# Mako_DSP_QuadFlash_and_Boot_R2_1.net
KiCad netlist of a schematic drawn in Altium Designer
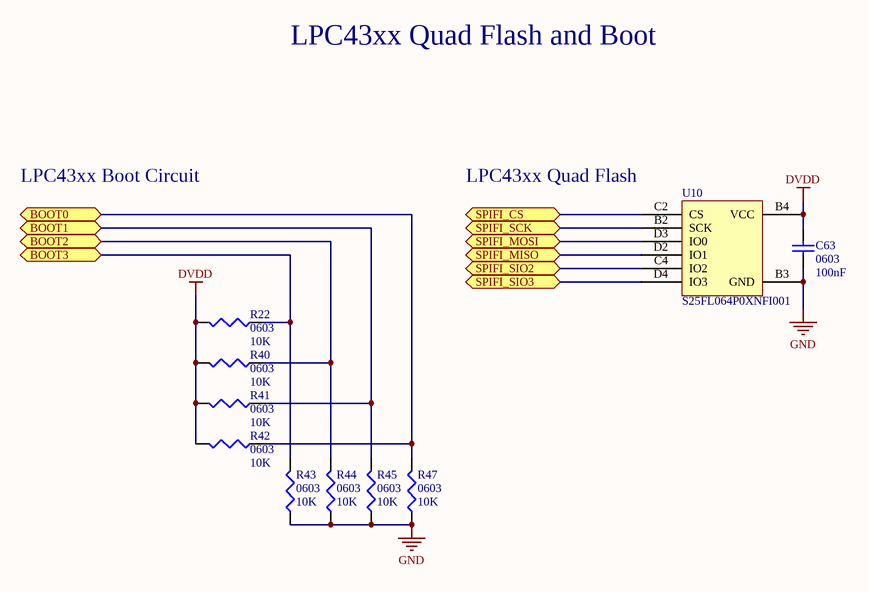
[diagram p0: Mako DSP QuadFlash and Boot R2.1.SchDoc]

(export (version "E")
  (design (tool "Eeschema 10.0.6"))
  (components
    (comp (ref "C63")
      (value "0603")
      (footprint "1608[0603]")
      (description "Capacitor (Semiconductor SIM Model)")
      (fields (field (name "ALTIUM_VALUE") "100nF") (field (name "PUBLISHER") "Altium Limited"))
      (libsource (lib "Miscellaneous Devices") (part "Cap Semi"))
    )
    (comp (ref "R22")
      (value "0603")
      (footprint "J1-0603")
      (description "Resistor")
      (fields (field (name "ALTIUM_VALUE") "10K") (field (name "PUBLISHER") "Altium Limited"))
      (libsource (lib "Miscellaneous Devices") (part "Res3"))
    )
    (comp (ref "R40")
      (value "0603")
      (footprint "J1-0603")
      (description "Resistor")
      (fields (field (name "ALTIUM_VALUE") "10K") (field (name "PUBLISHER") "Altium Limited"))
      (libsource (lib "Miscellaneous Devices") (part "Res3"))
    )
    (comp (ref "R41")
      (value "0603")
      (footprint "J1-0603")
      (description "Resistor")
      (fields (field (name "ALTIUM_VALUE") "10K") (field (name "PUBLISHER") "Altium Limited"))
      (libsource (lib "Miscellaneous Devices") (part "Res3"))
    )
    (comp (ref "R42")
      (value "0603")
      (footprint "J1-0603")
      (description "Resistor")
      (fields (field (name "ALTIUM_VALUE") "10K") (field (name "PUBLISHER") "Altium Limited"))
      (libsource (lib "Miscellaneous Devices") (part "Res3"))
    )
    (comp (ref "R43")
      (value "0603")
      (footprint "J1-0603")
      (description "Resistor")
      (fields (field (name "ALTIUM_VALUE") "10K") (field (name "PUBLISHER") "Altium Limited"))
      (libsource (lib "Miscellaneous Devices") (part "Res3"))
    )
    (comp (ref "R44")
      (value "0603")
      (footprint "J1-0603")
      (description "Resistor")
      (fields (field (name "ALTIUM_VALUE") "10K") (field (name "PUBLISHER") "Altium Limited"))
      (libsource (lib "Miscellaneous Devices") (part "Res3"))
    )
    (comp (ref "R45")
      (value "0603")
      (footprint "J1-0603")
      (description "Resistor")
      (fields (field (name "ALTIUM_VALUE") "10K") (field (name "PUBLISHER") "Altium Limited"))
      (libsource (lib "Miscellaneous Devices") (part "Res3"))
    )
    (comp (ref "R47")
      (value "0603")
      (footprint "J1-0603")
      (description "Resistor")
      (fields (field (name "ALTIUM_VALUE") "10K") (field (name "PUBLISHER") "Altium Limited"))
      (libsource (lib "Miscellaneous Devices") (part "Res3"))
    )
    (comp (ref "U10")
      (value "S25FL064P0XNFI001")
      (footprint "S25FL064P0XNFI001")
      (description "SPIFI Quad Flash")
      (libsource (lib "Mako DSP Schematic Library") (part "S25FL064P0XNFI001"))
    )
  )
  (nets
    (net (code "1") (name "/BOOT0") (class "Default")
      (node (ref "R42") (pin "1") (pinfunction "1_1") (pintype "passive"))
      (node (ref "R47") (pin "2") (pinfunction "2_2") (pintype "passive"))
    )
    (net (code "2") (name "/BOOT1") (class "Default")
      (node (ref "R41") (pin "1") (pinfunction "1_1") (pintype "passive"))
      (node (ref "R45") (pin "2") (pinfunction "2_2") (pintype "passive"))
    )
    (net (code "3") (name "/BOOT2") (class "Default")
      (node (ref "R40") (pin "1") (pinfunction "1_1") (pintype "passive"))
      (node (ref "R44") (pin "2") (pinfunction "2_2") (pintype "passive"))
    )
    (net (code "4") (name "/BOOT3") (class "Default")
      (node (ref "R22") (pin "1") (pinfunction "1_1") (pintype "passive"))
      (node (ref "R43") (pin "2") (pinfunction "2_2") (pintype "passive"))
    )
    (net (code "5") (name "/SPIFI_CS") (class "Default")
      (node (ref "U10") (pin "C2") (pinfunction "CS_C2") (pintype "passive"))
    )
    (net (code "6") (name "/SPIFI_MISO") (class "Default")
      (node (ref "U10") (pin "D2") (pinfunction "IO1_D2") (pintype "passive"))
    )
    (net (code "7") (name "/SPIFI_MOSI") (class "Default")
      (node (ref "U10") (pin "D3") (pinfunction "IO0_D3") (pintype "passive"))
    )
    (net (code "8") (name "/SPIFI_SCK") (class "Default")
      (node (ref "U10") (pin "B2") (pinfunction "SCK_B2") (pintype "passive"))
    )
    (net (code "9") (name "/SPIFI_SIO2") (class "Default")
      (node (ref "U10") (pin "C4") (pinfunction "IO2_C4") (pintype "passive"))
    )
    (net (code "10") (name "/SPIFI_SIO3") (class "Default")
      (node (ref "U10") (pin "D4") (pinfunction "IO3_D4") (pintype "passive"))
    )
    (net (code "11") (name "DVDD") (class "Default")
      (node (ref "C63") (pin "2") (pinfunction "2_2") (pintype "passive"))
      (node (ref "R22") (pin "2") (pinfunction "2_2") (pintype "passive"))
      (node (ref "R40") (pin "2") (pinfunction "2_2") (pintype "passive"))
      (node (ref "R41") (pin "2") (pinfunction "2_2") (pintype "passive"))
      (node (ref "R42") (pin "2") (pinfunction "2_2") (pintype "passive"))
      (node (ref "U10") (pin "B4") (pinfunction "VCC_B4") (pintype "passive"))
    )
    (net (code "12") (name "GND") (class "Default")
      (node (ref "C63") (pin "1") (pinfunction "1_1") (pintype "passive"))
      (node (ref "R43") (pin "1") (pinfunction "1_1") (pintype "passive"))
      (node (ref "R44") (pin "1") (pinfunction "1_1") (pintype "passive"))
      (node (ref "R45") (pin "1") (pinfunction "1_1") (pintype "passive"))
      (node (ref "R47") (pin "1") (pinfunction "1_1") (pintype "passive"))
      (node (ref "U10") (pin "B3") (pinfunction "GND_B3") (pintype "passive"))
    )
    (net (code "13") (name "unconnected-(U10-NC-PadA2)") (class "Default")
      (node (ref "U10") (pin "A2") (pinfunction "NC_A2") (pintype "passive"))
    )
    (net (code "14") (name "unconnected-(U10-NC-PadA3)") (class "Default")
      (node (ref "U10") (pin "A3") (pinfunction "NC_A3") (pintype "passive"))
    )
    (net (code "15") (name "unconnected-(U10-NC-PadA4)") (class "Default")
      (node (ref "U10") (pin "A4") (pinfunction "NC_A4") (pintype "passive"))
    )
    (net (code "16") (name "unconnected-(U10-NC-PadA5)") (class "Default")
      (node (ref "U10") (pin "A5") (pinfunction "NC_A5") (pintype "passive"))
    )
    (net (code "17") (name "unconnected-(U10-NC-PadB1)") (class "Default")
      (node (ref "U10") (pin "B1") (pinfunction "NC_B1") (pintype "passive"))
    )
    (net (code "18") (name "unconnected-(U10-NC-PadB5)") (class "Default")
      (node (ref "U10") (pin "B5") (pinfunction "NC_B5") (pintype "passive"))
    )
    (net (code "19") (name "unconnected-(U10-NC-PadC1)") (class "Default")
      (node (ref "U10") (pin "C1") (pinfunction "NC_C1") (pintype "passive"))
    )
    (net (code "20") (name "unconnected-(U10-NC-PadC5)") (class "Default")
      (node (ref "U10") (pin "C5") (pinfunction "NC_C5") (pintype "passive"))
    )
    (net (code "21") (name "unconnected-(U10-NC-PadD1)") (class "Default")
      (node (ref "U10") (pin "D1") (pinfunction "NC_D1") (pintype "passive"))
    )
    (net (code "22") (name "unconnected-(U10-NC-PadD5)") (class "Default")
      (node (ref "U10") (pin "D5") (pinfunction "NC_D5") (pintype "passive"))
    )
    (net (code "23") (name "unconnected-(U10-NC-PadE1)") (class "Default")
      (node (ref "U10") (pin "E1") (pinfunction "NC_E1") (pintype "passive"))
    )
    (net (code "24") (name "unconnected-(U10-NC-PadE2)") (class "Default")
      (node (ref "U10") (pin "E2") (pinfunction "NC_E2") (pintype "passive"))
    )
    (net (code "25") (name "unconnected-(U10-NC-PadE3)") (class "Default")
      (node (ref "U10") (pin "E3") (pinfunction "NC_E3") (pintype "passive"))
    )
    (net (code "26") (name "unconnected-(U10-NC-PadE4)") (class "Default")
      (node (ref "U10") (pin "E4") (pinfunction "NC_E4") (pintype "passive"))
    )
    (net (code "27") (name "unconnected-(U10-NC-PadE5)") (class "Default")
      (node (ref "U10") (pin "E5") (pinfunction "NC_E5") (pintype "passive"))
    )
  )
)
